# mega32_u4_simple_v2.net
KiCad netlist of a schematic drawn in EAGLE
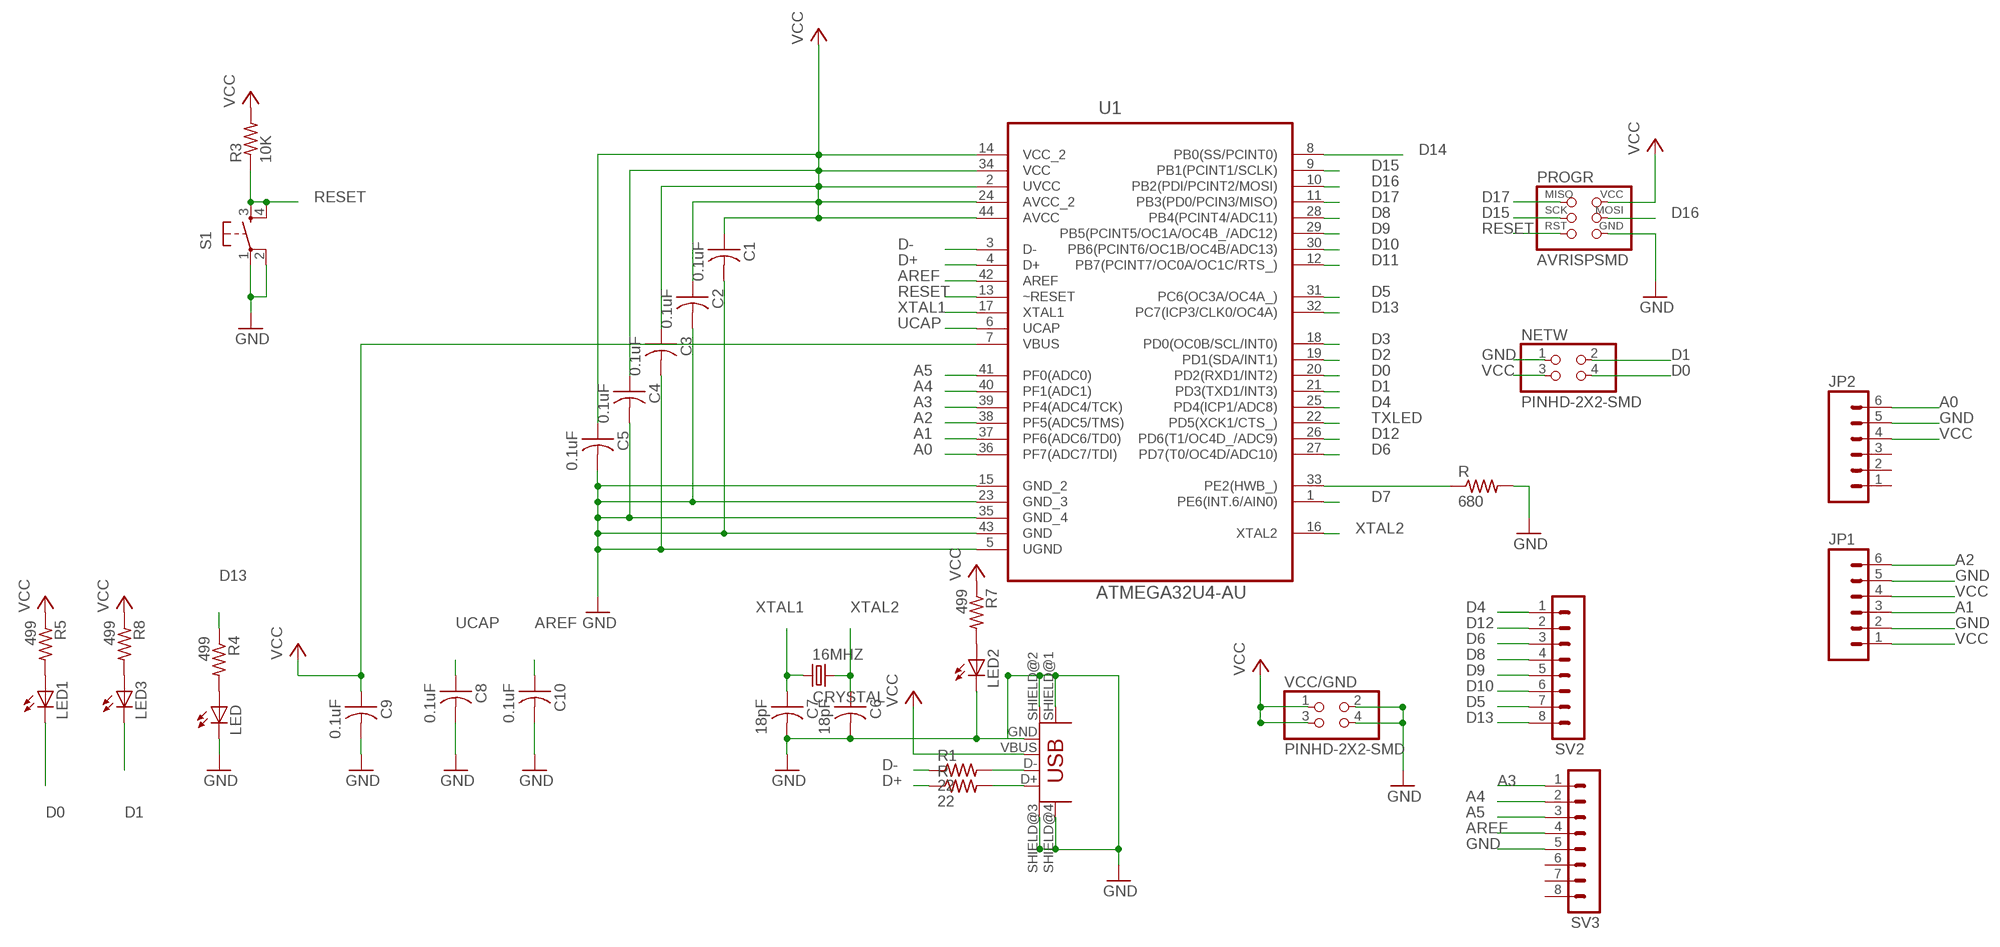
[diagram p0: schematic, sheet 1]

(export (version "E")
  (design (tool "Eeschema 10.0.6"))
  (components
    (comp (ref "16MHZ")
      (value "CRYSTAL")
      (footprint "eagle-import:2-SMD-5X3MM")
      (libsource (lib "eagle-import") (part "CRYSTAL"))
    )
    (comp (ref "C1")
      (value "0.1uF")
      (footprint "eagle-import:C1206FAB")
      (libsource (lib "eagle-import") (part "CAP-US1206FAB"))
    )
    (comp (ref "C2")
      (value "0.1uF")
      (footprint "eagle-import:C1206FAB")
      (libsource (lib "eagle-import") (part "CAP-US1206FAB"))
    )
    (comp (ref "C3")
      (value "0.1uF")
      (footprint "eagle-import:C1206FAB")
      (libsource (lib "eagle-import") (part "CAP-US1206FAB"))
    )
    (comp (ref "C4")
      (value "0.1uF")
      (footprint "eagle-import:C1206FAB")
      (libsource (lib "eagle-import") (part "CAP-US1206FAB"))
    )
    (comp (ref "C5")
      (value "0.1uF")
      (footprint "eagle-import:C1206FAB")
      (libsource (lib "eagle-import") (part "CAP-US1206FAB"))
    )
    (comp (ref "C6")
      (value "18pF")
      (footprint "eagle-import:C1206FAB")
      (libsource (lib "eagle-import") (part "CAP-US1206FAB"))
    )
    (comp (ref "C7")
      (value "18pF")
      (footprint "eagle-import:C1206FAB")
      (libsource (lib "eagle-import") (part "CAP-US1206FAB"))
    )
    (comp (ref "C8")
      (value "0.1uF")
      (footprint "eagle-import:C1206FAB")
      (libsource (lib "eagle-import") (part "CAP-US1206FAB"))
    )
    (comp (ref "C9")
      (value "0.1uF")
      (footprint "eagle-import:C1206FAB")
      (libsource (lib "eagle-import") (part "CAP-US1206FAB"))
    )
    (comp (ref "C10")
      (value "0.1uF")
      (footprint "eagle-import:C1206FAB")
      (libsource (lib "eagle-import") (part "CAP-US1206FAB"))
    )
    (comp (ref "JP1")
      (value "M06SMD")
      (footprint "eagle-import:1X06-SMD")
      (libsource (lib "eagle-import") (part "M06SMD"))
    )
    (comp (ref "JP2")
      (value "M06SMD")
      (footprint "eagle-import:1X06-SMD")
      (libsource (lib "eagle-import") (part "M06SMD"))
    )
    (comp (ref "LED")
      (value "LED1206")
      (footprint "eagle-import:1206")
      (libsource (lib "eagle-import") (part "LED1206"))
    )
    (comp (ref "LED1")
      (value "LED1206")
      (footprint "eagle-import:1206")
      (libsource (lib "eagle-import") (part "LED1206"))
    )
    (comp (ref "LED2")
      (value "LED1206")
      (footprint "eagle-import:1206")
      (libsource (lib "eagle-import") (part "LED1206"))
    )
    (comp (ref "LED3")
      (value "LED1206")
      (footprint "eagle-import:1206")
      (libsource (lib "eagle-import") (part "LED1206"))
    )
    (comp (ref "NETW")
      (value "PINHD-2X2-SMD")
      (footprint "eagle-import:2X02SMD")
      (libsource (lib "eagle-import") (part "PINHD-2X2-SMD"))
    )
    (comp (ref "PROGR")
      (value "AVRISPSMD")
      (footprint "eagle-import:2X03SMD")
      (libsource (lib "eagle-import") (part "AVRISPSMD"))
    )
    (comp (ref "R")
      (value "680")
      (footprint "eagle-import:R1206FAB")
      (libsource (lib "eagle-import") (part "RES-US1206FAB"))
    )
    (comp (ref "R.")
      (value "22")
      (footprint "eagle-import:R1206FAB")
      (libsource (lib "eagle-import") (part "RES-US1206FAB"))
    )
    (comp (ref "R1")
      (value "22")
      (footprint "eagle-import:R1206FAB")
      (libsource (lib "eagle-import") (part "RES-US1206FAB"))
    )
    (comp (ref "R3")
      (value "10K")
      (footprint "eagle-import:R1206FAB")
      (libsource (lib "eagle-import") (part "RES-US1206FAB"))
    )
    (comp (ref "R4")
      (value "499")
      (footprint "eagle-import:1206")
      (libsource (lib "eagle-import") (part "RESISTOR1206"))
    )
    (comp (ref "R5")
      (value "499")
      (footprint "eagle-import:1206")
      (libsource (lib "eagle-import") (part "RESISTOR1206"))
    )
    (comp (ref "R7")
      (value "499")
      (footprint "eagle-import:1206")
      (libsource (lib "eagle-import") (part "RESISTOR1206"))
    )
    (comp (ref "R8")
      (value "499")
      (footprint "eagle-import:1206")
      (libsource (lib "eagle-import") (part "RESISTOR1206"))
    )
    (comp (ref "S1")
      (value "6MM_SWITCH6MM_SWITCH")
      (footprint "eagle-import:6MM_SWITCH")
      (libsource (lib "eagle-import") (part "6MM_SWITCH6MM_SWITCH"))
    )
    (comp (ref "SV2")
      (value "MA08-1")
      (footprint "eagle-import:MA08-1")
      (libsource (lib "eagle-import") (part "MA08-1"))
    )
    (comp (ref "SV3")
      (value "MA08-1")
      (footprint "eagle-import:MA08-1")
      (libsource (lib "eagle-import") (part "MA08-1"))
    )
    (comp (ref "U$1")
      (value "USB_MINIB")
      (footprint "eagle-import:USB_MINIB")
      (libsource (lib "eagle-import") (part "USB_MINIB"))
    )
    (comp (ref "U1")
      (value "ATMEGA32U4-AU")
      (footprint "eagle-import:QFP80P1200X1200X120-44N")
      (libsource (lib "eagle-import") (part "ATMEGA32U4-AU"))
    )
    (comp (ref "VCC/GND")
      (value "PINHD-2X2-SMD")
      (footprint "eagle-import:2X02SMD")
      (libsource (lib "eagle-import") (part "PINHD-2X2-SMD"))
    )
  )
  (nets
    (net (code "1") (name "/A0") (class "Default")
      (node (ref "JP2") (pin "6") (pinfunction "6_6") (pintype "passive"))
      (node (ref "U1") (pin "36") (pinfunction "PF7(ADC7/TDI)_36") (pintype "bidirectional"))
    )
    (net (code "2") (name "/A1") (class "Default")
      (node (ref "JP1") (pin "3") (pinfunction "3_3") (pintype "passive"))
      (node (ref "U1") (pin "37") (pinfunction "PF6(ADC6/TD0)_37") (pintype "bidirectional"))
    )
    (net (code "3") (name "/A2") (class "Default")
      (node (ref "JP1") (pin "6") (pinfunction "6_6") (pintype "passive"))
      (node (ref "U1") (pin "38") (pinfunction "PF5(ADC5/TMS)_38") (pintype "bidirectional"))
    )
    (net (code "4") (name "/A3") (class "Default")
      (node (ref "SV3") (pin "1") (pinfunction "1_1") (pintype "passive"))
      (node (ref "U1") (pin "39") (pinfunction "PF4(ADC4/TCK)_39") (pintype "bidirectional"))
    )
    (net (code "5") (name "/A4") (class "Default")
      (node (ref "SV3") (pin "2") (pinfunction "2_2") (pintype "passive"))
      (node (ref "U1") (pin "40") (pinfunction "PF1(ADC1)_40") (pintype "bidirectional"))
    )
    (net (code "6") (name "/A5") (class "Default")
      (node (ref "SV3") (pin "3") (pinfunction "3_3") (pintype "passive"))
      (node (ref "U1") (pin "41") (pinfunction "PF0(ADC0)_41") (pintype "bidirectional"))
    )
    (net (code "7") (name "/AREF") (class "Default")
      (node (ref "C10") (pin "1") (pinfunction "1_1") (pintype "passive"))
      (node (ref "SV3") (pin "4") (pinfunction "4_4") (pintype "passive"))
      (node (ref "U1") (pin "42") (pinfunction "AREF_42") (pintype "input"))
    )
    (net (code "8") (name "/D+") (class "Default")
      (node (ref "R.") (pin "1") (pinfunction "1_1") (pintype "passive"))
      (node (ref "U1") (pin "4") (pinfunction "D+_4") (pintype "passive"))
    )
    (net (code "9") (name "/D-") (class "Default")
      (node (ref "R1") (pin "1") (pinfunction "1_1") (pintype "passive"))
      (node (ref "U1") (pin "3") (pinfunction "D-_3") (pintype "passive"))
    )
    (net (code "10") (name "/D0") (class "Default")
      (node (ref "LED1") (pin "2") (pinfunction "C_2") (pintype "passive"))
      (node (ref "NETW") (pin "4") (pinfunction "4_4") (pintype "passive"))
      (node (ref "U1") (pin "20") (pinfunction "PD2(RXD1/INT2)_20") (pintype "bidirectional"))
    )
    (net (code "11") (name "/D1") (class "Default")
      (node (ref "LED3") (pin "2") (pinfunction "C_2") (pintype "passive"))
      (node (ref "NETW") (pin "2") (pinfunction "2_2") (pintype "passive"))
      (node (ref "U1") (pin "21") (pinfunction "PD3(TXD1/INT3)_21") (pintype "bidirectional"))
    )
    (net (code "12") (name "/D2") (class "Default")
      (node (ref "U1") (pin "19") (pinfunction "PD1(SDA/INT1)_19") (pintype "bidirectional"))
    )
    (net (code "13") (name "/D3") (class "Default")
      (node (ref "U1") (pin "18") (pinfunction "PD0(OC0B/SCL/INT0)_18") (pintype "bidirectional"))
    )
    (net (code "14") (name "/D4") (class "Default")
      (node (ref "SV2") (pin "1") (pinfunction "1_1") (pintype "passive"))
      (node (ref "U1") (pin "25") (pinfunction "PD4(ICP1/ADC8)_25") (pintype "bidirectional"))
    )
    (net (code "15") (name "/D5") (class "Default")
      (node (ref "SV2") (pin "7") (pinfunction "7_7") (pintype "passive"))
      (node (ref "U1") (pin "31") (pinfunction "PC6(OC3A/OC4A_)_31") (pintype "bidirectional"))
    )
    (net (code "16") (name "/D6") (class "Default")
      (node (ref "SV2") (pin "3") (pinfunction "3_3") (pintype "passive"))
      (node (ref "U1") (pin "27") (pinfunction "PD7(T0/OC4D/ADC10)_27") (pintype "bidirectional"))
    )
    (net (code "17") (name "/D7") (class "Default")
      (node (ref "U1") (pin "1") (pinfunction "PE6(INT.6/AIN0)_1") (pintype "bidirectional"))
    )
    (net (code "18") (name "/D8") (class "Default")
      (node (ref "SV2") (pin "4") (pinfunction "4_4") (pintype "passive"))
      (node (ref "U1") (pin "28") (pinfunction "PB4(PCINT4/ADC11)_28") (pintype "bidirectional"))
    )
    (net (code "19") (name "/D9") (class "Default")
      (node (ref "SV2") (pin "5") (pinfunction "5_5") (pintype "passive"))
      (node (ref "U1") (pin "29") (pinfunction "PB5(PCINT5/OC1A/OC4B_/ADC12)_29") (pintype "bidirectional"))
    )
    (net (code "20") (name "/D10") (class "Default")
      (node (ref "SV2") (pin "6") (pinfunction "6_6") (pintype "passive"))
      (node (ref "U1") (pin "30") (pinfunction "PB6(PCINT6/OC1B/OC4B/ADC13)_30") (pintype "bidirectional"))
    )
    (net (code "21") (name "/D11") (class "Default")
      (node (ref "U1") (pin "12") (pinfunction "PB7(PCINT7/OC0A/OC1C/RTS_)_12") (pintype "bidirectional"))
    )
    (net (code "22") (name "/D12") (class "Default")
      (node (ref "SV2") (pin "2") (pinfunction "2_2") (pintype "passive"))
      (node (ref "U1") (pin "26") (pinfunction "PD6(T1/OC4D_/ADC9)_26") (pintype "bidirectional"))
    )
    (net (code "23") (name "/D13") (class "Default")
      (node (ref "R4") (pin "1") (pinfunction "1_1") (pintype "passive"))
      (node (ref "SV2") (pin "8") (pinfunction "8_8") (pintype "passive"))
      (node (ref "U1") (pin "32") (pinfunction "PC7(ICP3/CLK0/OC4A)_32") (pintype "bidirectional"))
    )
    (net (code "24") (name "/D14") (class "Default")
      (node (ref "U1") (pin "8") (pinfunction "PB0(SS/PCINT0)_8") (pintype "bidirectional"))
    )
    (net (code "25") (name "/D15") (class "Default")
      (node (ref "PROGR") (pin "3") (pinfunction "SCK_3") (pintype "passive"))
      (node (ref "U1") (pin "9") (pinfunction "PB1(PCINT1/SCLK)_9") (pintype "bidirectional"))
    )
    (net (code "26") (name "/D16") (class "Default")
      (node (ref "PROGR") (pin "4") (pinfunction "MOSI_4") (pintype "passive"))
      (node (ref "U1") (pin "10") (pinfunction "PB2(PDI/PCINT2/MOSI)_10") (pintype "bidirectional"))
    )
    (net (code "27") (name "/D17") (class "Default")
      (node (ref "PROGR") (pin "1") (pinfunction "MISO_1") (pintype "passive"))
      (node (ref "U1") (pin "11") (pinfunction "PB3(PD0/PCIN3/MISO)_11") (pintype "bidirectional"))
    )
    (net (code "28") (name "/RESET") (class "Default")
      (node (ref "PROGR") (pin "5") (pinfunction "RST_5") (pintype "passive"))
      (node (ref "R3") (pin "1") (pinfunction "1_1") (pintype "passive"))
      (node (ref "S1") (pin "3") (pinfunction "S_3") (pintype "passive"))
      (node (ref "S1") (pin "4") (pinfunction "S1_4") (pintype "passive"))
      (node (ref "U1") (pin "13") (pinfunction "~{RESET}_13") (pintype "input"))
    )
    (net (code "29") (name "/TXLED") (class "Default")
      (node (ref "U1") (pin "22") (pinfunction "PD5(XCK1/CTS_)_22") (pintype "bidirectional"))
    )
    (net (code "30") (name "/UCAP") (class "Default")
      (node (ref "C8") (pin "1") (pinfunction "1_1") (pintype "passive"))
      (node (ref "U1") (pin "6") (pinfunction "UCAP_6") (pintype "power_in"))
    )
    (net (code "31") (name "/XTAL1") (class "Default")
      (node (ref "16MHZ") (pin "P$1") (pinfunction "1_P$1") (pintype "passive"))
      (node (ref "C7") (pin "1") (pinfunction "1_1") (pintype "passive"))
      (node (ref "U1") (pin "17") (pinfunction "XTAL1_17") (pintype "input"))
    )
    (net (code "32") (name "/XTAL2") (class "Default")
      (node (ref "16MHZ") (pin "P$2") (pinfunction "2_P$2") (pintype "passive"))
      (node (ref "C6") (pin "1") (pinfunction "1_1") (pintype "passive"))
      (node (ref "U1") (pin "16") (pinfunction "XTAL2_16") (pintype "output"))
    )
    (net (code "33") (name "GND") (class "Default")
      (node (ref "C1") (pin "2") (pinfunction "2_2") (pintype "passive"))
      (node (ref "C10") (pin "2") (pinfunction "2_2") (pintype "passive"))
      (node (ref "C2") (pin "2") (pinfunction "2_2") (pintype "passive"))
      (node (ref "C3") (pin "2") (pinfunction "2_2") (pintype "passive"))
      (node (ref "C4") (pin "2") (pinfunction "2_2") (pintype "passive"))
      (node (ref "C5") (pin "2") (pinfunction "2_2") (pintype "passive"))
      (node (ref "C6") (pin "2") (pinfunction "2_2") (pintype "passive"))
      (node (ref "C7") (pin "2") (pinfunction "2_2") (pintype "passive"))
      (node (ref "C8") (pin "2") (pinfunction "2_2") (pintype "passive"))
      (node (ref "C9") (pin "2") (pinfunction "2_2") (pintype "passive"))
      (node (ref "JP1") (pin "2") (pinfunction "2_2") (pintype "passive"))
      (node (ref "JP1") (pin "5") (pinfunction "5_5") (pintype "passive"))
      (node (ref "JP2") (pin "5") (pinfunction "5_5") (pintype "passive"))
      (node (ref "LED") (pin "2") (pinfunction "C_2") (pintype "passive"))
      (node (ref "LED2") (pin "2") (pinfunction "C_2") (pintype "passive"))
      (node (ref "NETW") (pin "1") (pinfunction "1_1") (pintype "passive"))
      (node (ref "PROGR") (pin "6") (pinfunction "GND_6") (pintype "passive"))
      (node (ref "R") (pin "2") (pinfunction "2_2") (pintype "passive"))
      (node (ref "S1") (pin "1") (pinfunction "P_1") (pintype "passive"))
      (node (ref "S1") (pin "2") (pinfunction "P1_2") (pintype "passive"))
      (node (ref "SV3") (pin "5") (pinfunction "5_5") (pintype "passive"))
      (node (ref "U$1") (pin "GND") (pinfunction "GND_GND") (pintype "bidirectional"))
      (node (ref "U$1") (pin "SHIELD@1") (pinfunction "SHIELD_SHIELD@1") (pintype "passive"))
      (node (ref "U$1") (pin "SHIELD@2") (pinfunction "SHIELD1_SHIELD@2") (pintype "passive"))
      (node (ref "U$1") (pin "SHIELD@3") (pinfunction "SHIELD2_SHIELD@3") (pintype "passive"))
      (node (ref "U$1") (pin "SHIELD@4") (pinfunction "SHIELD3_SHIELD@4") (pintype "passive"))
      (node (ref "U1") (pin "15") (pinfunction "GND_2_15") (pintype "passive"))
      (node (ref "U1") (pin "23") (pinfunction "GND_3_23") (pintype "passive"))
      (node (ref "U1") (pin "35") (pinfunction "GND_4_35") (pintype "passive"))
      (node (ref "U1") (pin "43") (pinfunction "GND_43") (pintype "passive"))
      (node (ref "U1") (pin "5") (pinfunction "UGND_5") (pintype "passive"))
      (node (ref "VCC/GND") (pin "2") (pinfunction "2_2") (pintype "passive"))
      (node (ref "VCC/GND") (pin "4") (pinfunction "4_4") (pintype "passive"))
    )
    (net (code "34") (name "Net-(LED-A)") (class "Default")
      (node (ref "LED") (pin "1") (pinfunction "A_1") (pintype "passive"))
      (node (ref "R4") (pin "2") (pinfunction "2_2") (pintype "passive"))
    )
    (net (code "35") (name "Net-(LED1-A)") (class "Default")
      (node (ref "LED1") (pin "1") (pinfunction "A_1") (pintype "passive"))
      (node (ref "R5") (pin "2") (pinfunction "2_2") (pintype "passive"))
    )
    (net (code "36") (name "Net-(LED2-A)") (class "Default")
      (node (ref "LED2") (pin "1") (pinfunction "A_1") (pintype "passive"))
      (node (ref "R7") (pin "2") (pinfunction "2_2") (pintype "passive"))
    )
    (net (code "37") (name "Net-(LED3-A)") (class "Default")
      (node (ref "LED3") (pin "1") (pinfunction "A_1") (pintype "passive"))
      (node (ref "R8") (pin "2") (pinfunction "2_2") (pintype "passive"))
    )
    (net (code "38") (name "Net-(R.-Pad2)") (class "Default")
      (node (ref "R.") (pin "2") (pinfunction "2_2") (pintype "passive"))
      (node (ref "U$1") (pin "D+") (pinfunction "D+_D+") (pintype "bidirectional"))
    )
    (net (code "39") (name "Net-(R1-Pad2)") (class "Default")
      (node (ref "R1") (pin "2") (pinfunction "2_2") (pintype "passive"))
      (node (ref "U$1") (pin "D-") (pinfunction "D-_D-") (pintype "bidirectional"))
    )
    (net (code "40") (name "Net-(U1-PE2(HWB_))") (class "Default")
      (node (ref "R") (pin "1") (pinfunction "1_1") (pintype "passive"))
      (node (ref "U1") (pin "33") (pinfunction "PE2(HWB_)_33") (pintype "bidirectional"))
    )
    (net (code "41") (name "VCC") (class "Default")
      (node (ref "C1") (pin "1") (pinfunction "1_1") (pintype "passive"))
      (node (ref "C2") (pin "1") (pinfunction "1_1") (pintype "passive"))
      (node (ref "C3") (pin "1") (pinfunction "1_1") (pintype "passive"))
      (node (ref "C4") (pin "1") (pinfunction "1_1") (pintype "passive"))
      (node (ref "C5") (pin "1") (pinfunction "1_1") (pintype "passive"))
      (node (ref "C9") (pin "1") (pinfunction "1_1") (pintype "passive"))
      (node (ref "JP1") (pin "1") (pinfunction "1_1") (pintype "passive"))
      (node (ref "JP1") (pin "4") (pinfunction "4_4") (pintype "passive"))
      (node (ref "JP2") (pin "4") (pinfunction "4_4") (pintype "passive"))
      (node (ref "NETW") (pin "3") (pinfunction "3_3") (pintype "passive"))
      (node (ref "PROGR") (pin "2") (pinfunction "VCC_2") (pintype "passive"))
      (node (ref "R3") (pin "2") (pinfunction "2_2") (pintype "passive"))
      (node (ref "R5") (pin "1") (pinfunction "1_1") (pintype "passive"))
      (node (ref "R7") (pin "1") (pinfunction "1_1") (pintype "passive"))
      (node (ref "R8") (pin "1") (pinfunction "1_1") (pintype "passive"))
      (node (ref "U$1") (pin "VBUS") (pinfunction "VBUS_VBUS") (pintype "bidirectional"))
      (node (ref "U1") (pin "14") (pinfunction "VCC_2_14") (pintype "power_in"))
      (node (ref "U1") (pin "2") (pinfunction "UVCC_2") (pintype "power_in"))
      (node (ref "U1") (pin "24") (pinfunction "AVCC_2_24") (pintype "power_in"))
      (node (ref "U1") (pin "34") (pinfunction "VCC_34") (pintype "power_in"))
      (node (ref "U1") (pin "44") (pinfunction "AVCC_44") (pintype "power_in"))
      (node (ref "U1") (pin "7") (pinfunction "VBUS_7") (pintype "input"))
      (node (ref "VCC/GND") (pin "1") (pinfunction "1_1") (pintype "passive"))
      (node (ref "VCC/GND") (pin "3") (pinfunction "3_3") (pintype "passive"))
    )
    (net (code "42") (name "unconnected-(JP2-Pad1)") (class "Default")
      (node (ref "JP2") (pin "1") (pinfunction "1_1") (pintype "passive"))
    )
    (net (code "43") (name "unconnected-(JP2-Pad2)") (class "Default")
      (node (ref "JP2") (pin "2") (pinfunction "2_2") (pintype "passive"))
    )
    (net (code "44") (name "unconnected-(JP2-Pad3)") (class "Default")
      (node (ref "JP2") (pin "3") (pinfunction "3_3") (pintype "passive"))
    )
    (net (code "45") (name "unconnected-(SV3-Pad6)") (class "Default")
      (node (ref "SV3") (pin "6") (pinfunction "6_6") (pintype "passive"))
    )
    (net (code "46") (name "unconnected-(SV3-Pad7)") (class "Default")
      (node (ref "SV3") (pin "7") (pinfunction "7_7") (pintype "passive"))
    )
    (net (code "47") (name "unconnected-(SV3-Pad8)") (class "Default")
      (node (ref "SV3") (pin "8") (pinfunction "8_8") (pintype "passive"))
    )
  )
)
